# Led.net
KiCad netlist of a schematic drawn in Altium Designer
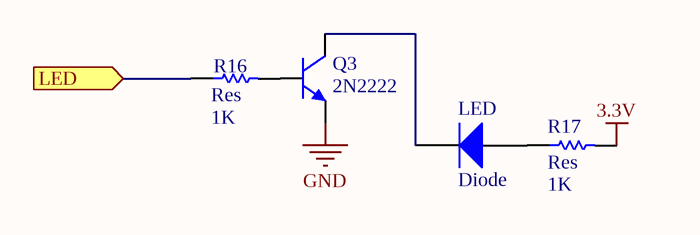
[diagram p0: Led.SchDoc]

(export (version "E")
  (design (tool "Eeschema 10.0.6"))
  (components
    (comp (ref "LED")
      (value "Diode")
      (footprint "2012[0805]")
      (description "1 Amp General Purpose Rectifier")
      (fields (field (name "PUBLISHER") "Altium Limited"))
      (libsource (lib "KN2CLib") (part "Diode"))
    )
    (comp (ref "Q3")
      (value "2N2222")
      (footprint "SOT-23")
      (description "NPN Bipolar Transistor")
      (fields (field (name "PUBLISHER") "Altium Limited"))
      (libsource (lib "KN2CLib") (part "2N2222"))
    )
    (comp (ref "R16")
      (value "Res")
      (footprint "2012[0805]")
      (description "Semiconductor Resistor")
      (fields (field (name "ALTIUM_VALUE") "1K") (field (name "PUBLISHER") "Altium Limited"))
      (libsource (lib "KN2CLib") (part "Res"))
    )
    (comp (ref "R17")
      (value "Res")
      (footprint "2012[0805]")
      (description "Semiconductor Resistor")
      (fields (field (name "ALTIUM_VALUE") "1K") (field (name "PUBLISHER") "Altium Limited"))
      (libsource (lib "KN2CLib") (part "Res"))
    )
  )
  (nets
    (net (code "1") (name "/LED") (class "Default")
      (node (ref "R16") (pin "1") (pinfunction "1_1") (pintype "passive"))
    )
    (net (code "2") (name "3.3V") (class "Default")
      (node (ref "R17") (pin "2") (pinfunction "2_2") (pintype "passive"))
    )
    (net (code "3") (name "GND") (class "Default")
      (node (ref "Q3") (pin "3") (pinfunction "E_3") (pintype "passive"))
    )
    (net (code "4") (name "Net-(LED-A)") (class "Default")
      (node (ref "LED") (pin "1") (pinfunction "A_1") (pintype "passive"))
      (node (ref "R17") (pin "1") (pinfunction "1_1") (pintype "passive"))
    )
    (net (code "5") (name "Net-(LED-K)") (class "Default")
      (node (ref "LED") (pin "2") (pinfunction "K_2") (pintype "passive"))
      (node (ref "Q3") (pin "1") (pinfunction "C_1") (pintype "passive"))
    )
    (net (code "6") (name "Net-(Q3-B)") (class "Default")
      (node (ref "Q3") (pin "2") (pinfunction "B_2") (pintype "passive"))
      (node (ref "R16") (pin "2") (pinfunction "2_2") (pintype "passive"))
    )
  )
)
